# Amp_Measure.net
KiCad netlist of a schematic drawn in EAGLE
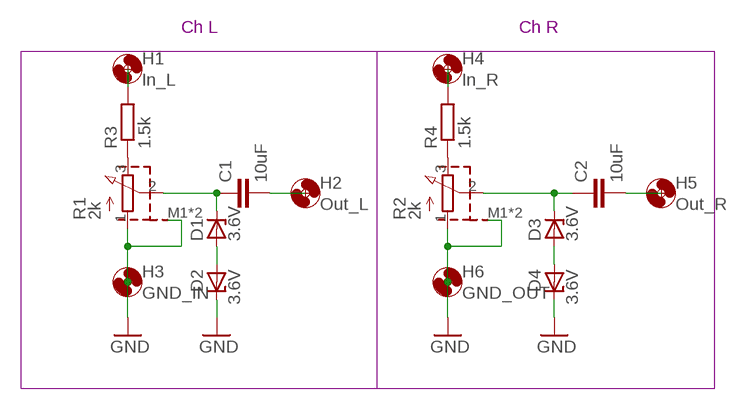
[diagram p0: schematic, sheet 1]

(export (version "E")
  (design (tool "Eeschema 10.0.6"))
  (components
    (comp (ref "C1")
      (value "10uF")
      (footprint "eagle-import:C0805K")
      (libsource (lib "eagle-import") (part "C-EUC0805K"))
    )
    (comp (ref "C2")
      (value "10uF")
      (footprint "eagle-import:C0805K")
      (libsource (lib "eagle-import") (part "C-EUC0805K"))
    )
    (comp (ref "D1")
      (value "3.6V")
      (footprint "eagle-import:SOD80C")
      (libsource (lib "eagle-import") (part "ZENER-DIODESOD80C"))
    )
    (comp (ref "D2")
      (value "3.6V")
      (footprint "eagle-import:SOD80C")
      (libsource (lib "eagle-import") (part "ZENER-DIODESOD80C"))
    )
    (comp (ref "D3")
      (value "3.6V")
      (footprint "eagle-import:SOD80C")
      (libsource (lib "eagle-import") (part "ZENER-DIODESOD80C"))
    )
    (comp (ref "D4")
      (value "3.6V")
      (footprint "eagle-import:SOD80C")
      (libsource (lib "eagle-import") (part "ZENER-DIODESOD80C"))
    )
    (comp (ref "H1")
      (value "In_L")
      (footprint "eagle-import:3,3")
      (libsource (lib "eagle-import") (part "MOUNT-HOLE3.3"))
    )
    (comp (ref "H2")
      (value "Out_L")
      (footprint "eagle-import:3,3")
      (libsource (lib "eagle-import") (part "MOUNT-HOLE3.3"))
    )
    (comp (ref "H3")
      (value "GND_IN")
      (footprint "eagle-import:3,3")
      (libsource (lib "eagle-import") (part "MOUNT-HOLE3.3"))
    )
    (comp (ref "H4")
      (value "In_R")
      (footprint "eagle-import:3,3")
      (libsource (lib "eagle-import") (part "MOUNT-HOLE3.3"))
    )
    (comp (ref "H5")
      (value "Out_R")
      (footprint "eagle-import:3,3")
      (libsource (lib "eagle-import") (part "MOUNT-HOLE3.3"))
    )
    (comp (ref "H6")
      (value "GND_OUT")
      (footprint "eagle-import:3,3")
      (libsource (lib "eagle-import") (part "MOUNT-HOLE3.3"))
    )
    (comp (ref "R1")
      (value "2k")
      (footprint "eagle-import:POTENT")
      (libsource (lib "eagle-import") (part "RS09-N-30"))
    )
    (comp (ref "R2")
      (value "2k")
      (footprint "eagle-import:POTENT")
      (libsource (lib "eagle-import") (part "RS09-N-30"))
    )
    (comp (ref "R3")
      (value "1.5k")
      (footprint "eagle-import:R0805W")
      (libsource (lib "eagle-import") (part "R-EU_R0805W"))
    )
    (comp (ref "R4")
      (value "1.5k")
      (footprint "eagle-import:R0805W")
      (libsource (lib "eagle-import") (part "R-EU_R0805W"))
    )
  )
  (nets
    (net (code "1") (name "GND") (class "Default")
      (node (ref "D2") (pin "C") (pinfunction "C_C") (pintype "passive"))
      (node (ref "D4") (pin "C") (pinfunction "C_C") (pintype "passive"))
      (node (ref "H3") (pin "P$1") (pinfunction "P$1_P$1") (pintype "bidirectional"))
      (node (ref "H6") (pin "P$1") (pinfunction "P$1_P$1") (pintype "bidirectional"))
      (node (ref "R1") (pin "1") (pinfunction "A_1") (pintype "passive"))
      (node (ref "R1") (pin "M1") (pinfunction "CASE_M1") (pintype "passive"))
      (node (ref "R1") (pin "M2") (pinfunction "CASE_M2") (pintype "passive"))
      (node (ref "R2") (pin "1") (pinfunction "A_1") (pintype "passive"))
      (node (ref "R2") (pin "M1") (pinfunction "CASE_M1") (pintype "passive"))
      (node (ref "R2") (pin "M2") (pinfunction "CASE_M2") (pintype "passive"))
    )
    (net (code "2") (name "Net-(C1-Pad2)") (class "Default")
      (node (ref "C1") (pin "2") (pinfunction "2_2") (pintype "passive"))
      (node (ref "H2") (pin "P$1") (pinfunction "P$1_P$1") (pintype "bidirectional"))
    )
    (net (code "3") (name "Net-(C2-Pad2)") (class "Default")
      (node (ref "C2") (pin "2") (pinfunction "2_2") (pintype "passive"))
      (node (ref "H5") (pin "P$1") (pinfunction "P$1_P$1") (pintype "bidirectional"))
    )
    (net (code "4") (name "Net-(D1-PadA)") (class "Default")
      (node (ref "D1") (pin "A") (pinfunction "A_A") (pintype "passive"))
      (node (ref "D2") (pin "A") (pinfunction "A_A") (pintype "passive"))
    )
    (net (code "5") (name "Net-(D3-PadA)") (class "Default")
      (node (ref "D3") (pin "A") (pinfunction "A_A") (pintype "passive"))
      (node (ref "D4") (pin "A") (pinfunction "A_A") (pintype "passive"))
    )
    (net (code "6") (name "Net-(H1-PadP$1)") (class "Default")
      (node (ref "H1") (pin "P$1") (pinfunction "P$1_P$1") (pintype "bidirectional"))
      (node (ref "R3") (pin "2") (pinfunction "2_2") (pintype "passive"))
    )
    (net (code "7") (name "Net-(H4-PadP$1)") (class "Default")
      (node (ref "H4") (pin "P$1") (pinfunction "P$1_P$1") (pintype "bidirectional"))
      (node (ref "R4") (pin "2") (pinfunction "2_2") (pintype "passive"))
    )
    (net (code "8") (name "Net-(R1-E)") (class "Default")
      (node (ref "R1") (pin "3") (pinfunction "E_3") (pintype "passive"))
      (node (ref "R3") (pin "1") (pinfunction "1_1") (pintype "passive"))
    )
    (net (code "9") (name "Net-(R1-S)") (class "Default")
      (node (ref "C1") (pin "1") (pinfunction "1_1") (pintype "passive"))
      (node (ref "D1") (pin "C") (pinfunction "C_C") (pintype "passive"))
      (node (ref "R1") (pin "2") (pinfunction "S_2") (pintype "passive"))
    )
    (net (code "10") (name "Net-(R2-E)") (class "Default")
      (node (ref "R2") (pin "3") (pinfunction "E_3") (pintype "passive"))
      (node (ref "R4") (pin "1") (pinfunction "1_1") (pintype "passive"))
    )
    (net (code "11") (name "Net-(R2-S)") (class "Default")
      (node (ref "C2") (pin "1") (pinfunction "1_1") (pintype "passive"))
      (node (ref "D3") (pin "C") (pinfunction "C_C") (pintype "passive"))
      (node (ref "R2") (pin "2") (pinfunction "S_2") (pintype "passive"))
    )
  )
)
